# Triggers.net
KiCad netlist of a schematic drawn in Altium Designer
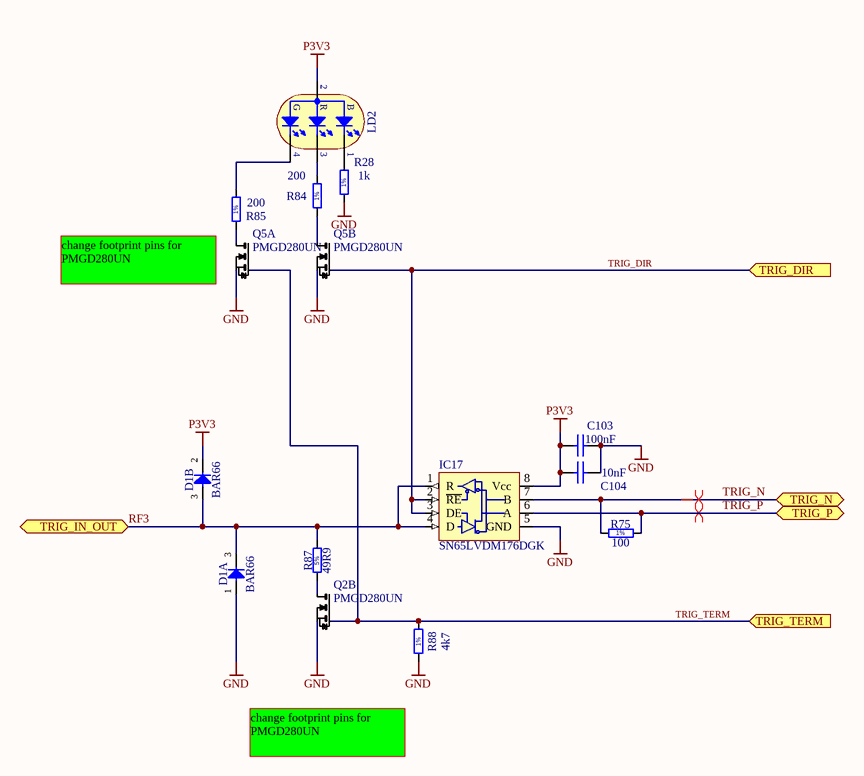
[diagram p0: Triggers.SchDoc]

(export (version "E")
  (design (tool "Eeschema 10.0.6"))
  (components
    (comp (ref "C103")
      (value "100nF")
      (footprint "CAPC0603X33N")
      (description "Non-polarised capacitor")
      (fields
        (field (name "PART NUMBER") "CC0201_100NF_6.3V_10%_X5R")
        (field (name "VOLTAGE") "6.3V")
        (field (name "AUTHOR") "CERN DEM JLC")
      )
      (libsource (lib "Capacitors") (part "Capacitor - non polarized"))
    )
    (comp (ref "C104")
      (value "10nF")
      (footprint "CAPC0603X33N")
      (description "Non-polarised capacitor")
      (fields
        (field (name "PART NUMBER") "CC0201_10NF_10V_10%_X5R")
        (field (name "VOLTAGE") "10V")
        (field (name "AUTHOR") "CERN DEM JLC")
      )
      (libsource (lib "Capacitors") (part "Capacitor - non polarized"))
    )
    (comp (ref "D1")
      (value "BAR66")
      (footprint "SOT95P240X110-3N")
      (description "Serial Diode")
      (fields
        (field (name "VOLTAGE") "150V")
        (field (name "POWER") "250mA")
        (field (name "AUTHOR") "CERN DEM JLC")
      )
      (libsource (lib "ICs And Semiconductors") (part "Diode x2 A1C3_A3C2"))
    )
    (comp (ref "IC17")
      (value "SN65LVDM176DGK")
      (footprint "MSOP8 TI/AD")
      (description "High Speed Differential Transceiver LVDS/LVTTL")
      (libsource (lib "Buffers & Drivers") (part "SN65LVDM176"))
    )
    (comp (ref "LD2")
      (value "Blue/Red/Green")
      (footprint "LED_AVAGO_HSMF-C113")
      (description "Tricolor LEDs 1 Cathode Blue, 2 Common Anode, 3 Cathode Red, 4 Cathode Green")
      (fields
        (field (name "PART NUMBER") "LED_AVAGO_HSMF-C113")
        (field (name "MANUFACTURER") "AVAGO TECHNOLOGIES")
        (field (name "AUTHOR") "CERN DEM JLC")
      )
      (libsource (lib "ICs And Semiconductors") (part "LED Blue-Red-Green 1CB_2AC_3CR_4CG"))
    )
    (comp (ref "Q2")
      (value "PMGD280UN")
      (footprint "SOT-363")
      (description "Dual NMOS 20V,08.A, 340mR, Vt=0.7V")
      (libsource (lib "LIBRARY_SCH") (part "Q_PMGD280UN"))
    )
    (comp (ref "Q5")
      (value "PMGD280UN")
      (footprint "SOT-363")
      (description "Dual NMOS 20V,08.A, 340mR, Vt=0.7V")
      (libsource (lib "LIBRARY_SCH") (part "Q_PMGD280UN"))
    )
    (comp (ref "R28")
      (value "1k")
      (footprint "RESC1005X40N")
      (description "Resistor - 1%")
      (fields
        (field (name "PART NUMBER") "R0402_1K_1%_0.0625W_100PPM")
        (field (name "POWER") "0.0625W")
        (field (name "AUTHOR") "CERN DEM JLC")
      )
      (libsource (lib "Resistors") (part "Resistor - 1%"))
    )
    (comp (ref "R75")
      (value "100")
      (footprint "RESC1005X40N")
      (description "Resistor - 1%")
      (fields
        (field (name "PART NUMBER") "R0402_100R_1%_0.0625W_100PPM")
        (field (name "POWER") "0.0625W")
        (field (name "AUTHOR") "CERN DEM JLC")
      )
      (libsource (lib "Resistors") (part "Resistor - 1%"))
    )
    (comp (ref "R84")
      (value "200")
      (footprint "RESC1005X40N")
      (description "Resistor - 1%")
      (fields
        (field (name "PART NUMBER") "R0402_200R_1%_0.0625W_100PPM")
        (field (name "POWER") "0.0625W")
        (field (name "AUTHOR") "CERN DEM JLC")
      )
      (libsource (lib "Resistors") (part "Resistor - 1%"))
    )
    (comp (ref "R85")
      (value "200")
      (footprint "RESC1005X40N")
      (description "Resistor - 1%")
      (fields
        (field (name "PART NUMBER") "R0402_200R_1%_0.0625W_100PPM")
        (field (name "POWER") "0.0625W")
        (field (name "AUTHOR") "CERN DEM JLC")
      )
      (libsource (lib "Resistors") (part "Resistor - 1%"))
    )
    (comp (ref "R87")
      (value "49R9")
      (footprint "RESC3225X70N")
      (description "Resistor - 5%")
      (fields
        (field (name "PART NUMBER") "R1210_49R9_1%_0.33W_100PPM")
        (field (name "POWER") "0.33W")
        (field (name "AUTHOR") "CERN DEM JLC")
      )
      (libsource (lib "Resistors") (part "Resistor - 5%"))
    )
    (comp (ref "R88")
      (value "4k7")
      (footprint "RESC1005X40N")
      (description "Resistor - 1%")
      (fields
        (field (name "PART NUMBER") "R0402_4K7_1%_0.0625W_100PPM")
        (field (name "POWER") "0.0625W")
        (field (name "AUTHOR") "CERN DEM JLC")
      )
      (libsource (lib "Resistors") (part "Resistor - 1%"))
    )
  )
  (nets
    (net (code "1") (name "/RF3") (class "Default")
      (node (ref "D1") (pin "3") (pinfunction "COMAC_3") (pintype "passive"))
      (node (ref "IC17") (pin "1") (pinfunction "R_1") (pintype "output"))
      (node (ref "IC17") (pin "4") (pinfunction "D_4") (pintype "input"))
      (node (ref "R87") (pin "2") (pinfunction "2_2") (pintype "passive"))
    )
    (net (code "2") (name "/TRIG_DIR") (class "Default")
      (node (ref "IC17") (pin "2") (pinfunction "~{RE}_2") (pintype "input"))
      (node (ref "IC17") (pin "3") (pinfunction "DE_3") (pintype "input"))
      (node (ref "Q5") (pin "5") (pinfunction "G2_5") (pintype "input"))
    )
    (net (code "3") (name "/TRIG_N") (class "Default")
      (node (ref "IC17") (pin "7") (pinfunction "B_7") (pintype "bidirectional"))
      (node (ref "R75") (pin "1") (pinfunction "1_1") (pintype "passive"))
    )
    (net (code "4") (name "/TRIG_P") (class "Default")
      (node (ref "IC17") (pin "6") (pinfunction "A_6") (pintype "bidirectional"))
      (node (ref "R75") (pin "2") (pinfunction "2_2") (pintype "passive"))
    )
    (net (code "5") (name "/TRIG_TERM") (class "Default")
      (node (ref "Q2") (pin "5") (pinfunction "G2_5") (pintype "input"))
      (node (ref "Q5") (pin "2") (pinfunction "G1_2") (pintype "input"))
      (node (ref "R88") (pin "2") (pinfunction "2_2") (pintype "passive"))
    )
    (net (code "6") (name "GND") (class "Default")
      (node (ref "C103") (pin "2") (pinfunction "2_2") (pintype "passive"))
      (node (ref "C104") (pin "2") (pinfunction "2_2") (pintype "passive"))
      (node (ref "D1") (pin "1") (pinfunction "A_1") (pintype "passive"))
      (node (ref "IC17") (pin "5") (pinfunction "GND_5") (pintype "power_in"))
      (node (ref "Q2") (pin "4") (pinfunction "S2_4") (pintype "open_emitter"))
      (node (ref "Q5") (pin "1") (pinfunction "S1_1") (pintype "open_emitter"))
      (node (ref "Q5") (pin "4") (pinfunction "S2_4") (pintype "open_emitter"))
      (node (ref "R28") (pin "1") (pinfunction "1_1") (pintype "passive"))
      (node (ref "R88") (pin "1") (pinfunction "1_1") (pintype "passive"))
    )
    (net (code "7") (name "Net-(LD2-CB)") (class "Default")
      (node (ref "LD2") (pin "1") (pinfunction "CB_1") (pintype "passive"))
      (node (ref "R28") (pin "2") (pinfunction "2_2") (pintype "passive"))
    )
    (net (code "8") (name "Net-(LD2-CG)") (class "Default")
      (node (ref "LD2") (pin "4") (pinfunction "CG_4") (pintype "passive"))
      (node (ref "R85") (pin "2") (pinfunction "2_2") (pintype "passive"))
    )
    (net (code "9") (name "Net-(LD2-CR)") (class "Default")
      (node (ref "LD2") (pin "3") (pinfunction "CR_3") (pintype "passive"))
      (node (ref "R84") (pin "2") (pinfunction "2_2") (pintype "passive"))
    )
    (net (code "10") (name "Net-(Q2B-D2)") (class "Default")
      (node (ref "Q2") (pin "3") (pinfunction "D2_3") (pintype "open_collector"))
      (node (ref "R87") (pin "1") (pinfunction "1_1") (pintype "passive"))
    )
    (net (code "11") (name "Net-(Q5A-D1)") (class "Default")
      (node (ref "Q5") (pin "6") (pinfunction "D1_6") (pintype "open_collector"))
      (node (ref "R85") (pin "1") (pinfunction "1_1") (pintype "passive"))
    )
    (net (code "12") (name "Net-(Q5B-D2)") (class "Default")
      (node (ref "Q5") (pin "3") (pinfunction "D2_3") (pintype "open_collector"))
      (node (ref "R84") (pin "1") (pinfunction "1_1") (pintype "passive"))
    )
    (net (code "13") (name "P3V3") (class "Default")
      (node (ref "C103") (pin "1") (pinfunction "1_1") (pintype "passive"))
      (node (ref "C104") (pin "1") (pinfunction "1_1") (pintype "passive"))
      (node (ref "D1") (pin "2") (pinfunction "C_2") (pintype "passive"))
      (node (ref "IC17") (pin "8") (pinfunction "Vcc_8") (pintype "power_in"))
      (node (ref "LD2") (pin "2") (pinfunction "AC_2") (pintype "passive"))
    )
  )
)
